# RN42.net
KiCad netlist of a schematic drawn in Altium Designer
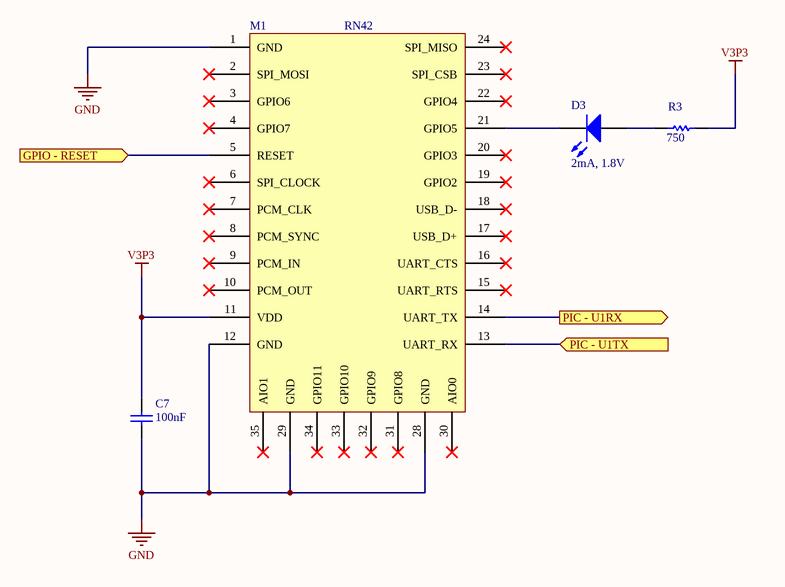
[diagram p0: RN42.SchDoc]

(export (version "E")
  (design (tool "Eeschema 10.0.6"))
  (components
    (comp (ref "C7")
      (value "100nF")
      (footprint "CAP 0603")
      (description "Capacitor")
      (fields (field (name "Comment") "Cap"))
      (libsource (lib "Miscellaneous Devices") (part "Cap"))
    )
    (comp (ref "D3")
      (value "2mA, 1.8V")
      (footprint "LED")
      (description "Typical INFRARED GaAs LED")
      (libsource (lib "Miscellaneous Devices") (part "LED0"))
    )
    (comp (ref "M1")
      (value "RN42")
      (footprint "RN42")
      (description "RN42 Bluetooth Module by Roven Networks")
      (libsource (lib "Schematics_Library") (part "RN42"))
    )
    (comp (ref "R3")
      (value "750")
      (footprint "RES 0603")
      (description "Resistor")
      (libsource (lib "Miscellaneous Devices") (part "Res1"))
    )
  )
  (nets
    (net (code "1") (name "/GPIO - RESET") (class "Default")
      (node (ref "M1") (pin "5") (pinfunction "RESET_5") (pintype "passive"))
    )
    (net (code "2") (name "/PIC - U1RX") (class "Default")
      (node (ref "M1") (pin "14") (pinfunction "UART_TX_14") (pintype "passive"))
    )
    (net (code "3") (name "/PIC - U1TX") (class "Default")
      (node (ref "M1") (pin "13") (pinfunction "UART_RX_13") (pintype "passive"))
    )
    (net (code "4") (name "GND") (class "Default")
      (node (ref "C7") (pin "1") (pinfunction "1_1") (pintype "passive"))
      (node (ref "M1") (pin "1") (pinfunction "GND_1") (pintype "passive"))
      (node (ref "M1") (pin "12") (pinfunction "GND_12") (pintype "passive"))
      (node (ref "M1") (pin "28") (pinfunction "GND_28") (pintype "passive"))
      (node (ref "M1") (pin "29") (pinfunction "GND_29") (pintype "passive"))
    )
    (net (code "5") (name "Net-(D3-A)") (class "Default")
      (node (ref "D3") (pin "1") (pinfunction "A_1") (pintype "passive"))
      (node (ref "R3") (pin "1") (pinfunction "1_1") (pintype "passive"))
    )
    (net (code "6") (name "Net-(D3-K)") (class "Default")
      (node (ref "D3") (pin "2") (pinfunction "K_2") (pintype "passive"))
      (node (ref "M1") (pin "21") (pinfunction "GPIO5_21") (pintype "passive"))
    )
    (net (code "7") (name "V3P3") (class "Default")
      (node (ref "C7") (pin "2") (pinfunction "2_2") (pintype "passive"))
      (node (ref "M1") (pin "11") (pinfunction "VDD_11") (pintype "passive"))
      (node (ref "R3") (pin "2") (pinfunction "2_2") (pintype "passive"))
    )
    (net (code "8") (name "unconnected-(M1-AIO0-Pad30)") (class "Default")
      (node (ref "M1") (pin "30") (pinfunction "AIO0_30") (pintype "passive+no_connect"))
    )
    (net (code "9") (name "unconnected-(M1-AIO1-Pad35)") (class "Default")
      (node (ref "M1") (pin "35") (pinfunction "AIO1_35") (pintype "passive+no_connect"))
    )
    (net (code "10") (name "unconnected-(M1-GPIO2-Pad19)") (class "Default")
      (node (ref "M1") (pin "19") (pinfunction "GPIO2_19") (pintype "passive+no_connect"))
    )
    (net (code "11") (name "unconnected-(M1-GPIO3-Pad20)") (class "Default")
      (node (ref "M1") (pin "20") (pinfunction "GPIO3_20") (pintype "passive+no_connect"))
    )
    (net (code "12") (name "unconnected-(M1-GPIO4-Pad22)") (class "Default")
      (node (ref "M1") (pin "22") (pinfunction "GPIO4_22") (pintype "passive+no_connect"))
    )
    (net (code "13") (name "unconnected-(M1-GPIO6-Pad3)") (class "Default")
      (node (ref "M1") (pin "3") (pinfunction "GPIO6_3") (pintype "passive+no_connect"))
    )
    (net (code "14") (name "unconnected-(M1-GPIO7-Pad4)") (class "Default")
      (node (ref "M1") (pin "4") (pinfunction "GPIO7_4") (pintype "passive+no_connect"))
    )
    (net (code "15") (name "unconnected-(M1-GPIO8-Pad31)") (class "Default")
      (node (ref "M1") (pin "31") (pinfunction "GPIO8_31") (pintype "passive+no_connect"))
    )
    (net (code "16") (name "unconnected-(M1-GPIO9-Pad32)") (class "Default")
      (node (ref "M1") (pin "32") (pinfunction "GPIO9_32") (pintype "passive+no_connect"))
    )
    (net (code "17") (name "unconnected-(M1-GPIO10-Pad33)") (class "Default")
      (node (ref "M1") (pin "33") (pinfunction "GPIO10_33") (pintype "passive+no_connect"))
    )
    (net (code "18") (name "unconnected-(M1-GPIO11-Pad34)") (class "Default")
      (node (ref "M1") (pin "34") (pinfunction "GPIO11_34") (pintype "passive+no_connect"))
    )
    (net (code "19") (name "unconnected-(M1-PCM_CLK-Pad7)") (class "Default")
      (node (ref "M1") (pin "7") (pinfunction "PCM_CLK_7") (pintype "passive+no_connect"))
    )
    (net (code "20") (name "unconnected-(M1-PCM_IN-Pad9)") (class "Default")
      (node (ref "M1") (pin "9") (pinfunction "PCM_IN_9") (pintype "passive+no_connect"))
    )
    (net (code "21") (name "unconnected-(M1-PCM_OUT-Pad10)") (class "Default")
      (node (ref "M1") (pin "10") (pinfunction "PCM_OUT_10") (pintype "passive+no_connect"))
    )
    (net (code "22") (name "unconnected-(M1-PCM_SYNC-Pad8)") (class "Default")
      (node (ref "M1") (pin "8") (pinfunction "PCM_SYNC_8") (pintype "passive+no_connect"))
    )
    (net (code "23") (name "unconnected-(M1-SPI_CLOCK-Pad6)") (class "Default")
      (node (ref "M1") (pin "6") (pinfunction "SPI_CLOCK_6") (pintype "passive+no_connect"))
    )
    (net (code "24") (name "unconnected-(M1-SPI_CSB-Pad23)") (class "Default")
      (node (ref "M1") (pin "23") (pinfunction "SPI_CSB_23") (pintype "passive+no_connect"))
    )
    (net (code "25") (name "unconnected-(M1-SPI_MISO-Pad24)") (class "Default")
      (node (ref "M1") (pin "24") (pinfunction "SPI_MISO_24") (pintype "passive+no_connect"))
    )
    (net (code "26") (name "unconnected-(M1-SPI_MOSI-Pad2)") (class "Default")
      (node (ref "M1") (pin "2") (pinfunction "SPI_MOSI_2") (pintype "passive+no_connect"))
    )
    (net (code "27") (name "unconnected-(M1-UART_CTS-Pad16)") (class "Default")
      (node (ref "M1") (pin "16") (pinfunction "UART_CTS_16") (pintype "passive+no_connect"))
    )
    (net (code "28") (name "unconnected-(M1-UART_RTS-Pad15)") (class "Default")
      (node (ref "M1") (pin "15") (pinfunction "UART_RTS_15") (pintype "passive+no_connect"))
    )
    (net (code "29") (name "unconnected-(M1-USB_D+-Pad17)") (class "Default")
      (node (ref "M1") (pin "17") (pinfunction "USB_D+_17") (pintype "passive+no_connect"))
    )
    (net (code "30") (name "unconnected-(M1-USB_D--Pad18)") (class "Default")
      (node (ref "M1") (pin "18") (pinfunction "USB_D-_18") (pintype "passive+no_connect"))
    )
  )
)
